# SmartRFv_25_06_15_PS.net
KiCad netlist of a schematic drawn in EAGLE
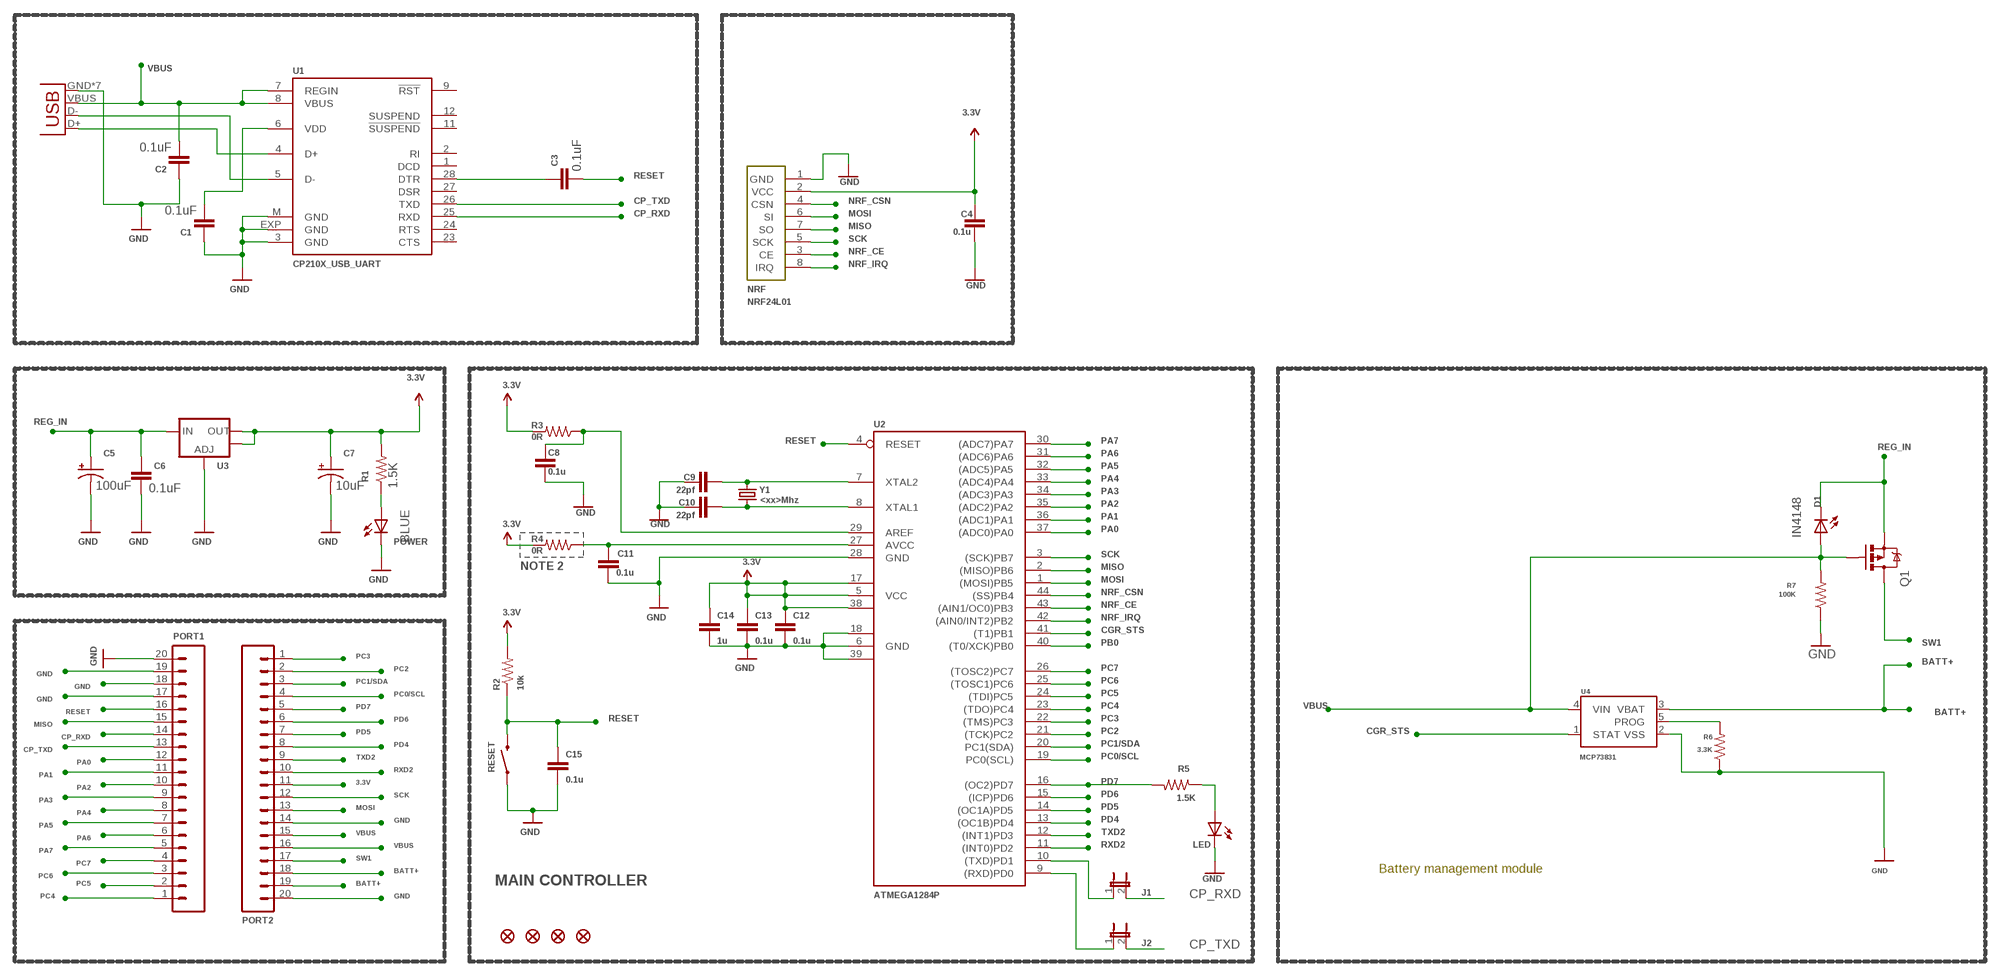
[diagram p0: schematic, sheet 1]

(export (version "E")
  (design (tool "Eeschema 10.0.6"))
  (components
    (comp (ref "C1")
      (value "0.1uF")
      (footprint "eagle-import:0805")
      (libsource (lib "eagle-import") (part "SparkFun-Passives_CAP0805"))
    )
    (comp (ref "C2")
      (value "0.1uF")
      (footprint "eagle-import:0805")
      (libsource (lib "eagle-import") (part "SparkFun-Passives_CAP0805"))
    )
    (comp (ref "C3")
      (value "0.1uF")
      (footprint "eagle-import:0805")
      (libsource (lib "eagle-import") (part "SparkFun-Passives_CAP0805"))
    )
    (comp (ref "C4")
      (value "0.1u")
      (footprint "eagle-import:0805")
      (libsource (lib "eagle-import") (part "CAP0805"))
    )
    (comp (ref "C5")
      (value "100uF")
      (footprint "eagle-import:EIA3216-KIT")
      (libsource (lib "eagle-import") (part "CAP_POL1206-KIT"))
    )
    (comp (ref "C6")
      (value "0.1uF")
      (footprint "eagle-import:0805")
      (libsource (lib "eagle-import") (part "SparkFun-Passives_CAP0805"))
    )
    (comp (ref "C7")
      (value "10uF")
      (footprint "eagle-import:EIA3216-KIT")
      (libsource (lib "eagle-import") (part "CAP_POL1206-KIT"))
    )
    (comp (ref "C8")
      (value "0.1u")
      (footprint "eagle-import:0805")
      (libsource (lib "eagle-import") (part "CAP0805"))
    )
    (comp (ref "C9")
      (value "22pf")
      (footprint "eagle-import:0805")
      (libsource (lib "eagle-import") (part "CAP0805"))
    )
    (comp (ref "C10")
      (value "22pf")
      (footprint "eagle-import:0805")
      (libsource (lib "eagle-import") (part "CAP0805"))
    )
    (comp (ref "C11")
      (value "0.1u")
      (footprint "eagle-import:0805")
      (libsource (lib "eagle-import") (part "CAP0805"))
    )
    (comp (ref "C12")
      (value "0.1u")
      (footprint "eagle-import:0805")
      (libsource (lib "eagle-import") (part "CAP0805"))
    )
    (comp (ref "C13")
      (value "0.1u")
      (footprint "eagle-import:0805")
      (libsource (lib "eagle-import") (part "CAP0805"))
    )
    (comp (ref "C14")
      (value "1u")
      (footprint "eagle-import:0805")
      (libsource (lib "eagle-import") (part "CAP0805"))
    )
    (comp (ref "C15")
      (value "0.1u")
      (footprint "eagle-import:0805")
      (libsource (lib "eagle-import") (part "CAP0805"))
    )
    (comp (ref "D1")
      (value "IN4148")
      (footprint "eagle-import:LED-1206")
      (libsource (lib "eagle-import") (part "LED1206"))
    )
    (comp (ref "FID1")
      (value "FIDUCIAL1X2")
      (footprint "eagle-import:FIDUCIAL-1X2")
      (libsource (lib "eagle-import") (part "FIDUCIAL1X2"))
    )
    (comp (ref "FID2")
      (value "FIDUCIAL1X2")
      (footprint "eagle-import:FIDUCIAL-1X2")
      (libsource (lib "eagle-import") (part "FIDUCIAL1X2"))
    )
    (comp (ref "FID3")
      (value "FIDUCIAL1X2")
      (footprint "eagle-import:FIDUCIAL-1X2")
      (libsource (lib "eagle-import") (part "FIDUCIAL1X2"))
    )
    (comp (ref "FID4")
      (value "FIDUCIAL1X2")
      (footprint "eagle-import:FIDUCIAL-1X2")
      (libsource (lib "eagle-import") (part "FIDUCIAL1X2"))
    )
    (comp (ref "J1")
      (value "JUMPER-2SMD-NC")
      (footprint "eagle-import:SJ_2S")
      (libsource (lib "eagle-import") (part "JUMPER-2SMD-NC"))
    )
    (comp (ref "J2")
      (value "JUMPER-2SMD-NC")
      (footprint "eagle-import:SJ_2S")
      (libsource (lib "eagle-import") (part "JUMPER-2SMD-NC"))
    )
    (comp (ref "LED")
      (value "LED")
      (footprint "eagle-import:LED-0805")
      (libsource (lib "eagle-import") (part "LED"))
    )
    (comp (ref "NRF")
      (value "NRF2401")
      (footprint "eagle-import:NRF2401")
      (fields (field (name "MFR_PN") "NRF24L01"))
      (libsource (lib "eagle-import") (part "NRF2401"))
    )
    (comp (ref "PORT1")
      (value "M20")
      (footprint "eagle-import:1X20")
      (libsource (lib "eagle-import") (part "M20"))
    )
    (comp (ref "PORT2")
      (value "M20")
      (footprint "eagle-import:1X20")
      (libsource (lib "eagle-import") (part "M20"))
    )
    (comp (ref "POWER")
      (value "BLUE")
      (footprint "eagle-import:LED-0805")
      (libsource (lib "eagle-import") (part "LED"))
    )
    (comp (ref "Q1")
      (value "MOSFET-PCHANNELSMD")
      (footprint "eagle-import:SOT23-3")
      (libsource (lib "eagle-import") (part "MOSFET-PCHANNELSMD"))
    )
    (comp (ref "R1")
      (value "1.5K")
      (footprint "eagle-import:0805")
      (libsource (lib "eagle-import") (part "RESISTOR0805-RES"))
    )
    (comp (ref "R2")
      (value "10k")
      (footprint "eagle-import:0805")
      (libsource (lib "eagle-import") (part "RESISTOR0805-RES"))
    )
    (comp (ref "R3")
      (value "0R")
      (footprint "eagle-import:0805")
      (libsource (lib "eagle-import") (part "RESISTOR0805-RES"))
    )
    (comp (ref "R4")
      (value "0R")
      (footprint "eagle-import:0805")
      (libsource (lib "eagle-import") (part "RESISTOR0805-RES"))
    )
    (comp (ref "R5")
      (value "1.5K")
      (footprint "eagle-import:0805")
      (libsource (lib "eagle-import") (part "RESISTOR0805-RES"))
    )
    (comp (ref "R6")
      (value "3.3K")
      (footprint "eagle-import:0805")
      (libsource (lib "eagle-import") (part "RESISTOR0805-RES"))
    )
    (comp (ref "R7")
      (value "100K")
      (footprint "eagle-import:0805")
      (libsource (lib "eagle-import") (part "RESISTOR0805-RES"))
    )
    (comp (ref "RESET")
      (value "SWITCH-MOMENTARY-2-SMD-1101NE")
      (footprint "eagle-import:TACTILE-SWITCH-1101NE")
      (libsource (lib "eagle-import") (part "SWITCH-MOMENTARY-2-SMD-1101NE"))
    )
    (comp (ref "U1")
      (value "CP210X_USB_UART")
      (footprint "eagle-import:MLP28")
      (libsource (lib "eagle-import") (part "CP210X_USB_UART"))
    )
    (comp (ref "U2")
      (value "MEGA32-A")
      (footprint "eagle-import:TQFP44")
      (fields (field (name "MPN") "ATMEGA32-16AU") (field (name "MPN_1") "ATMEGA1284P"))
      (libsource (lib "eagle-import") (part "MEGA32-A"))
    )
    (comp (ref "U3")
      (value "V_REG_LM1117SOT223")
      (footprint "eagle-import:SOT223")
      (libsource (lib "eagle-import") (part "V_REG_LM1117SOT223"))
    )
    (comp (ref "U4")
      (value "MCP73831")
      (footprint "eagle-import:SOT23-5")
      (libsource (lib "eagle-import") (part "MCP73831"))
    )
    (comp (ref "USB")
      (value "USB-MICROB")
      (footprint "eagle-import:USB-MICROB")
      (libsource (lib "eagle-import") (part "USB-MICROB"))
    )
    (comp (ref "Y1")
      (value "<xx>Mhz")
      (footprint "eagle-import:CRYSTAL-SMD-5X3")
      (libsource (lib "eagle-import") (part "CRYSTAL5X3"))
    )
  )
  (nets
    (net (code "1") (name "/BATT+") (class "Default")
      (node (ref "PORT2") (pin "18") (pinfunction "18_18") (pintype "passive"))
      (node (ref "PORT2") (pin "19") (pinfunction "19_19") (pintype "passive"))
      (node (ref "U4") (pin "3") (pinfunction "VBAT_3") (pintype "power_in"))
    )
    (net (code "2") (name "/CGR_STS") (class "Default")
      (node (ref "U2") (pin "41") (pinfunction "(T1)PB1_41") (pintype "bidirectional"))
      (node (ref "U4") (pin "1") (pinfunction "STAT_1") (pintype "output"))
    )
    (net (code "3") (name "/CP_RXD") (class "Default")
      (node (ref "J1") (pin "2") (pinfunction "2_2") (pintype "passive"))
      (node (ref "PORT1") (pin "14") (pinfunction "14_14") (pintype "passive"))
      (node (ref "U1") (pin "25") (pinfunction "RXD_25") (pintype "input"))
    )
    (net (code "4") (name "/CP_TXD") (class "Default")
      (node (ref "J2") (pin "2") (pinfunction "2_2") (pintype "passive"))
      (node (ref "PORT1") (pin "13") (pinfunction "13_13") (pintype "passive"))
      (node (ref "U1") (pin "26") (pinfunction "TXD_26") (pintype "output"))
    )
    (net (code "5") (name "/MISO") (class "Default")
      (node (ref "NRF") (pin "7") (pinfunction "SO_7") (pintype "bidirectional"))
      (node (ref "PORT1") (pin "15") (pinfunction "15_15") (pintype "passive"))
      (node (ref "U2") (pin "2") (pinfunction "(MISO)PB6_2") (pintype "bidirectional"))
    )
    (net (code "6") (name "/MOSI") (class "Default")
      (node (ref "NRF") (pin "6") (pinfunction "SI_6") (pintype "bidirectional"))
      (node (ref "PORT2") (pin "13") (pinfunction "13_13") (pintype "passive"))
      (node (ref "U2") (pin "1") (pinfunction "(MOSI)PB5_1") (pintype "bidirectional"))
    )
    (net (code "7") (name "/NRF_CE") (class "Default")
      (node (ref "NRF") (pin "3") (pinfunction "CE_3") (pintype "bidirectional"))
      (node (ref "U2") (pin "43") (pinfunction "(AIN1/OC0)PB3_43") (pintype "bidirectional"))
    )
    (net (code "8") (name "/NRF_CSN") (class "Default")
      (node (ref "NRF") (pin "4") (pinfunction "CSN_4") (pintype "bidirectional"))
      (node (ref "U2") (pin "44") (pinfunction "(SS)PB4_44") (pintype "bidirectional"))
    )
    (net (code "9") (name "/NRF_IRQ") (class "Default")
      (node (ref "NRF") (pin "8") (pinfunction "IRQ_8") (pintype "bidirectional"))
      (node (ref "U2") (pin "42") (pinfunction "(AIN0/INT2)PB2_42") (pintype "bidirectional"))
    )
    (net (code "10") (name "/PA0") (class "Default")
      (node (ref "PORT1") (pin "12") (pinfunction "12_12") (pintype "passive"))
      (node (ref "U2") (pin "37") (pinfunction "(ADC0)PA0_37") (pintype "bidirectional"))
    )
    (net (code "11") (name "/PA1") (class "Default")
      (node (ref "PORT1") (pin "11") (pinfunction "11_11") (pintype "passive"))
      (node (ref "U2") (pin "36") (pinfunction "(ADC1)PA1_36") (pintype "bidirectional"))
    )
    (net (code "12") (name "/PA2") (class "Default")
      (node (ref "PORT1") (pin "10") (pinfunction "10_10") (pintype "passive"))
      (node (ref "U2") (pin "35") (pinfunction "(ADC2)PA2_35") (pintype "bidirectional"))
    )
    (net (code "13") (name "/PA3") (class "Default")
      (node (ref "PORT1") (pin "9") (pinfunction "9_9") (pintype "passive"))
      (node (ref "U2") (pin "34") (pinfunction "(ADC3)PA3_34") (pintype "bidirectional"))
    )
    (net (code "14") (name "/PA4") (class "Default")
      (node (ref "PORT1") (pin "8") (pinfunction "8_8") (pintype "passive"))
      (node (ref "U2") (pin "33") (pinfunction "(ADC4)PA4_33") (pintype "bidirectional"))
    )
    (net (code "15") (name "/PA5") (class "Default")
      (node (ref "PORT1") (pin "7") (pinfunction "7_7") (pintype "passive"))
      (node (ref "U2") (pin "32") (pinfunction "(ADC5)PA5_32") (pintype "bidirectional"))
    )
    (net (code "16") (name "/PA6") (class "Default")
      (node (ref "PORT1") (pin "6") (pinfunction "6_6") (pintype "passive"))
      (node (ref "U2") (pin "31") (pinfunction "(ADC6)PA6_31") (pintype "bidirectional"))
    )
    (net (code "17") (name "/PA7") (class "Default")
      (node (ref "PORT1") (pin "5") (pinfunction "5_5") (pintype "passive"))
      (node (ref "U2") (pin "30") (pinfunction "(ADC7)PA7_30") (pintype "bidirectional"))
    )
    (net (code "18") (name "/PB0") (class "Default")
      (node (ref "U2") (pin "40") (pinfunction "(T0/XCK)PB0_40") (pintype "bidirectional"))
    )
    (net (code "19") (name "/PC0{slash}SCL") (class "Default")
      (node (ref "PORT2") (pin "4") (pinfunction "4_4") (pintype "passive"))
      (node (ref "U2") (pin "19") (pinfunction "PC0(SCL)_19") (pintype "bidirectional"))
    )
    (net (code "20") (name "/PC1{slash}SDA") (class "Default")
      (node (ref "PORT2") (pin "3") (pinfunction "3_3") (pintype "passive"))
      (node (ref "U2") (pin "20") (pinfunction "PC1(SDA)_20") (pintype "bidirectional"))
    )
    (net (code "21") (name "/PC2") (class "Default")
      (node (ref "PORT2") (pin "2") (pinfunction "2_2") (pintype "passive"))
      (node (ref "U2") (pin "21") (pinfunction "(TCK)PC2_21") (pintype "bidirectional"))
    )
    (net (code "22") (name "/PC3") (class "Default")
      (node (ref "PORT2") (pin "1") (pinfunction "1_1") (pintype "passive"))
      (node (ref "U2") (pin "22") (pinfunction "(TMS)PC3_22") (pintype "bidirectional"))
    )
    (net (code "23") (name "/PC4") (class "Default")
      (node (ref "PORT1") (pin "1") (pinfunction "1_1") (pintype "passive"))
      (node (ref "U2") (pin "23") (pinfunction "(TDO)PC4_23") (pintype "bidirectional"))
    )
    (net (code "24") (name "/PC5") (class "Default")
      (node (ref "PORT1") (pin "2") (pinfunction "2_2") (pintype "passive"))
      (node (ref "U2") (pin "24") (pinfunction "(TDI)PC5_24") (pintype "bidirectional"))
    )
    (net (code "25") (name "/PC6") (class "Default")
      (node (ref "PORT1") (pin "3") (pinfunction "3_3") (pintype "passive"))
      (node (ref "U2") (pin "25") (pinfunction "(TOSC1)PC6_25") (pintype "bidirectional"))
    )
    (net (code "26") (name "/PC7") (class "Default")
      (node (ref "PORT1") (pin "4") (pinfunction "4_4") (pintype "passive"))
      (node (ref "U2") (pin "26") (pinfunction "(TOSC2)PC7_26") (pintype "bidirectional"))
    )
    (net (code "27") (name "/PD4") (class "Default")
      (node (ref "PORT2") (pin "8") (pinfunction "8_8") (pintype "passive"))
      (node (ref "U2") (pin "13") (pinfunction "(OC1B)PD4_13") (pintype "bidirectional"))
    )
    (net (code "28") (name "/PD5") (class "Default")
      (node (ref "PORT2") (pin "7") (pinfunction "7_7") (pintype "passive"))
      (node (ref "U2") (pin "14") (pinfunction "(OC1A)PD5_14") (pintype "bidirectional"))
    )
    (net (code "29") (name "/PD6") (class "Default")
      (node (ref "PORT2") (pin "6") (pinfunction "6_6") (pintype "passive"))
      (node (ref "U2") (pin "15") (pinfunction "(ICP)PD6_15") (pintype "bidirectional"))
    )
    (net (code "30") (name "/PD7") (class "Default")
      (node (ref "PORT2") (pin "5") (pinfunction "5_5") (pintype "passive"))
      (node (ref "R5") (pin "2") (pinfunction "2_2") (pintype "passive"))
      (node (ref "U2") (pin "16") (pinfunction "(OC2)PD7_16") (pintype "bidirectional"))
    )
    (net (code "31") (name "/REG_IN") (class "Default")
      (node (ref "C5") (pin "A") (pinfunction "+_A") (pintype "passive"))
      (node (ref "C6") (pin "1") (pinfunction "1_1") (pintype "passive"))
      (node (ref "D1") (pin "C") (pinfunction "C_C") (pintype "passive"))
      (node (ref "Q1") (pin "2") (pinfunction "S_2") (pintype "passive"))
      (node (ref "U3") (pin "3") (pinfunction "IN_3") (pintype "input"))
    )
    (net (code "32") (name "/RESET") (class "Default")
      (node (ref "C15") (pin "1") (pinfunction "1_1") (pintype "passive"))
      (node (ref "C3") (pin "2") (pinfunction "2_2") (pintype "passive"))
      (node (ref "PORT1") (pin "16") (pinfunction "16_16") (pintype "passive"))
      (node (ref "R2") (pin "1") (pinfunction "1_1") (pintype "passive"))
      (node (ref "RESET") (pin "P$2") (pinfunction "2_P$2") (pintype "passive"))
      (node (ref "U2") (pin "4") (pinfunction "RESET_4") (pintype "input"))
    )
    (net (code "33") (name "/RXD2") (class "Default")
      (node (ref "PORT2") (pin "10") (pinfunction "10_10") (pintype "passive"))
      (node (ref "U2") (pin "11") (pinfunction "(INT0)PD2_11") (pintype "bidirectional"))
    )
    (net (code "34") (name "/SCK") (class "Default")
      (node (ref "NRF") (pin "5") (pinfunction "SCK_5") (pintype "bidirectional"))
      (node (ref "PORT2") (pin "12") (pinfunction "12_12") (pintype "passive"))
      (node (ref "U2") (pin "3") (pinfunction "(SCK)PB7_3") (pintype "bidirectional"))
    )
    (net (code "35") (name "/SW1") (class "Default")
      (node (ref "PORT2") (pin "17") (pinfunction "17_17") (pintype "passive"))
      (node (ref "Q1") (pin "3") (pinfunction "D_3") (pintype "passive"))
    )
    (net (code "36") (name "/TXD2") (class "Default")
      (node (ref "PORT2") (pin "9") (pinfunction "9_9") (pintype "passive"))
      (node (ref "U2") (pin "12") (pinfunction "(INT1)PD3_12") (pintype "bidirectional"))
    )
    (net (code "37") (name "/VBUS") (class "Default")
      (node (ref "C2") (pin "2") (pinfunction "2_2") (pintype "passive"))
      (node (ref "D1") (pin "A") (pinfunction "A_A") (pintype "passive"))
      (node (ref "PORT2") (pin "15") (pinfunction "15_15") (pintype "passive"))
      (node (ref "PORT2") (pin "16") (pinfunction "16_16") (pintype "passive"))
      (node (ref "Q1") (pin "1") (pinfunction "G_1") (pintype "passive"))
      (node (ref "R7") (pin "2") (pinfunction "2_2") (pintype "passive"))
      (node (ref "U1") (pin "7") (pinfunction "REGIN_7") (pintype "passive"))
      (node (ref "U1") (pin "8") (pinfunction "VBUS_8") (pintype "input"))
      (node (ref "U4") (pin "4") (pinfunction "VIN_4") (pintype "power_in"))
      (node (ref "USB") (pin "VBUS") (pinfunction "VBUS_VBUS") (pintype "bidirectional"))
    )
    (net (code "38") (name "3.3V") (class "Default")
      (node (ref "C12") (pin "1") (pinfunction "1_1") (pintype "passive"))
      (node (ref "C13") (pin "1") (pinfunction "1_1") (pintype "passive"))
      (node (ref "C14") (pin "1") (pinfunction "1_1") (pintype "passive"))
      (node (ref "C4") (pin "2") (pinfunction "2_2") (pintype "passive"))
      (node (ref "C7") (pin "A") (pinfunction "+_A") (pintype "passive"))
      (node (ref "NRF") (pin "2") (pinfunction "VCC_2") (pintype "bidirectional"))
      (node (ref "PORT2") (pin "11") (pinfunction "11_11") (pintype "passive"))
      (node (ref "R1") (pin "2") (pinfunction "2_2") (pintype "passive"))
      (node (ref "R2") (pin "2") (pinfunction "2_2") (pintype "passive"))
      (node (ref "R3") (pin "2") (pinfunction "2_2") (pintype "passive"))
      (node (ref "R4") (pin "2") (pinfunction "2_2") (pintype "passive"))
      (node (ref "U2") (pin "17") (pinfunction "VCC1_17") (pintype "power_in"))
      (node (ref "U2") (pin "38") (pinfunction "VCC2_38") (pintype "power_in"))
      (node (ref "U2") (pin "5") (pinfunction "VCC_5") (pintype "power_in"))
      (node (ref "U3") (pin "2") (pinfunction "OUT_2") (pintype "output"))
      (node (ref "U3") (pin "4") (pinfunction "OUT_4") (pintype "output"))
    )
    (net (code "39") (name "GND") (class "Default")
      (node (ref "C1") (pin "1") (pinfunction "1_1") (pintype "passive"))
      (node (ref "C10") (pin "1") (pinfunction "1_1") (pintype "passive"))
      (node (ref "C11") (pin "2") (pinfunction "2_2") (pintype "passive"))
      (node (ref "C12") (pin "2") (pinfunction "2_2") (pintype "passive"))
      (node (ref "C13") (pin "2") (pinfunction "2_2") (pintype "passive"))
      (node (ref "C14") (pin "2") (pinfunction "2_2") (pintype "passive"))
      (node (ref "C15") (pin "2") (pinfunction "2_2") (pintype "passive"))
      (node (ref "C2") (pin "1") (pinfunction "1_1") (pintype "passive"))
      (node (ref "C4") (pin "1") (pinfunction "1_1") (pintype "passive"))
      (node (ref "C5") (pin "C") (pinfunction "-_C") (pintype "passive"))
      (node (ref "C6") (pin "2") (pinfunction "2_2") (pintype "passive"))
      (node (ref "C7") (pin "C") (pinfunction "-_C") (pintype "passive"))
      (node (ref "C8") (pin "2") (pinfunction "2_2") (pintype "passive"))
      (node (ref "C9") (pin "1") (pinfunction "1_1") (pintype "passive"))
      (node (ref "LED") (pin "2") (pinfunction "C_2") (pintype "passive"))
      (node (ref "NRF") (pin "1") (pinfunction "GND_1") (pintype "bidirectional"))
      (node (ref "PORT1") (pin "17") (pinfunction "17_17") (pintype "passive"))
      (node (ref "PORT1") (pin "18") (pinfunction "18_18") (pintype "passive"))
      (node (ref "PORT1") (pin "19") (pinfunction "19_19") (pintype "passive"))
      (node (ref "PORT1") (pin "20") (pinfunction "20_20") (pintype "passive"))
      (node (ref "PORT2") (pin "14") (pinfunction "14_14") (pintype "passive"))
      (node (ref "PORT2") (pin "20") (pinfunction "20_20") (pintype "passive"))
      (node (ref "POWER") (pin "2") (pinfunction "C_2") (pintype "passive"))
      (node (ref "R6") (pin "1") (pinfunction "1_1") (pintype "passive"))
      (node (ref "R7") (pin "1") (pinfunction "1_1") (pintype "passive"))
      (node (ref "RESET") (pin "P$1") (pinfunction "1_P$1") (pintype "passive"))
      (node (ref "U1") (pin "3") (pinfunction "GND_3") (pintype "power_in"))
      (node (ref "U1") (pin "EXP") (pinfunction "GND_EXP") (pintype "power_in"))
      (node (ref "U1") (pin "M") (pinfunction "GND_M") (pintype "power_in"))
      (node (ref "U2") (pin "18") (pinfunction "GND1_18") (pintype "power_in"))
      (node (ref "U2") (pin "28") (pinfunction "GND_28") (pintype "power_in"))
      (node (ref "U2") (pin "39") (pinfunction "GND2_39") (pintype "power_in"))
      (node (ref "U2") (pin "6") (pinfunction "GND_6") (pintype "power_in"))
      (node (ref "U3") (pin "1") (pinfunction "ADJ_1") (pintype "input"))
      (node (ref "U4") (pin "2") (pinfunction "VSS_2") (pintype "power_in"))
      (node (ref "USB") (pin "GND") (pinfunction "GND_GND") (pintype "bidirectional"))
      (node (ref "USB") (pin "MT1") (pinfunction "GND_MT1") (pintype "bidirectional"))
      (node (ref "USB") (pin "MT2") (pinfunction "GND_MT2") (pintype "bidirectional"))
      (node (ref "USB") (pin "MT3") (pinfunction "GND_MT3") (pintype "bidirectional"))
      (node (ref "USB") (pin "MT4") (pinfunction "GND_MT4") (pintype "bidirectional"))
      (node (ref "USB") (pin "P$1") (pinfunction "GND_P$1") (pintype "bidirectional"))
      (node (ref "USB") (pin "P$2") (pinfunction "GND_P$2") (pintype "bidirectional"))
    )
    (net (code "40") (name "Net-(LED-A)") (class "Default")
      (node (ref "LED") (pin "1") (pinfunction "A_1") (pintype "passive"))
      (node (ref "R5") (pin "1") (pinfunction "1_1") (pintype "passive"))
    )
    (net (code "41") (name "Net-(POWER-A)") (class "Default")
      (node (ref "POWER") (pin "1") (pinfunction "A_1") (pintype "passive"))
      (node (ref "R1") (pin "1") (pinfunction "1_1") (pintype "passive"))
    )
    (net (code "42") (name "Net-(U1-D+)") (class "Default")
      (node (ref "U1") (pin "4") (pinfunction "D+_4") (pintype "bidirectional"))
      (node (ref "USB") (pin "D+") (pinfunction "D+_D+") (pintype "bidirectional"))
    )
    (net (code "43") (name "Net-(U1-D-)") (class "Default")
      (node (ref "U1") (pin "5") (pinfunction "D-_5") (pintype "bidirectional"))
      (node (ref "USB") (pin "D-") (pinfunction "D-_D-") (pintype "bidirectional"))
    )
    (net (code "44") (name "Net-(U1-DTR)") (class "Default")
      (node (ref "C3") (pin "1") (pinfunction "1_1") (pintype "passive"))
      (node (ref "U1") (pin "28") (pinfunction "DTR_28") (pintype "output"))
    )
    (net (code "45") (name "Net-(U1-VDD)") (class "Default")
      (node (ref "C1") (pin "2") (pinfunction "2_2") (pintype "passive"))
      (node (ref "U1") (pin "6") (pinfunction "VDD_6") (pintype "power_in"))
    )
    (net (code "46") (name "Net-(U2-(RXD)PD0)") (class "Default")
      (node (ref "J2") (pin "1") (pinfunction "1_1") (pintype "passive"))
      (node (ref "U2") (pin "9") (pinfunction "(RXD)PD0_9") (pintype "bidirectional"))
    )
    (net (code "47") (name "Net-(U2-(TXD)PD1)") (class "Default")
      (node (ref "J1") (pin "1") (pinfunction "1_1") (pintype "passive"))
      (node (ref "U2") (pin "10") (pinfunction "(TXD)PD1_10") (pintype "bidirectional"))
    )
    (net (code "48") (name "Net-(U2-AREF)") (class "Default")
      (node (ref "C8") (pin "1") (pinfunction "1_1") (pintype "passive"))
      (node (ref "R3") (pin "1") (pinfunction "1_1") (pintype "passive"))
      (node (ref "U2") (pin "29") (pinfunction "AREF_29") (pintype "passive"))
    )
    (net (code "49") (name "Net-(U2-AVCC)") (class "Default")
      (node (ref "C11") (pin "1") (pinfunction "1_1") (pintype "passive"))
      (node (ref "R4") (pin "1") (pinfunction "1_1") (pintype "passive"))
      (node (ref "U2") (pin "27") (pinfunction "AVCC_27") (pintype "power_in"))
    )
    (net (code "50") (name "Net-(U2-XTAL1)") (class "Default")
      (node (ref "C10") (pin "2") (pinfunction "2_2") (pintype "passive"))
      (node (ref "U2") (pin "8") (pinfunction "XTAL1_8") (pintype "bidirectional"))
      (node (ref "Y1") (pin "1") (pinfunction "1_1") (pintype "passive"))
    )
    (net (code "51") (name "Net-(U2-XTAL2)") (class "Default")
      (node (ref "C9") (pin "2") (pinfunction "2_2") (pintype "passive"))
      (node (ref "U2") (pin "7") (pinfunction "XTAL2_7") (pintype "bidirectional"))
      (node (ref "Y1") (pin "3") (pinfunction "2_3") (pintype "passive"))
    )
    (net (code "52") (name "Net-(U4-PROG)") (class "Default")
      (node (ref "R6") (pin "2") (pinfunction "2_2") (pintype "passive"))
      (node (ref "U4") (pin "5") (pinfunction "PROG_5") (pintype "input"))
    )
    (net (code "53") (name "unconnected-(U1-CTS-Pad23)") (class "Default")
      (node (ref "U1") (pin "23") (pinfunction "CTS_23") (pintype "input"))
    )
    (net (code "54") (name "unconnected-(U1-DCD-Pad1)") (class "Default")
      (node (ref "U1") (pin "1") (pinfunction "DCD_1") (pintype "input"))
    )
    (net (code "55") (name "unconnected-(U1-DSR-Pad27)") (class "Default")
      (node (ref "U1") (pin "27") (pinfunction "DSR_27") (pintype "input"))
    )
    (net (code "56") (name "unconnected-(U1-RI-Pad2)") (class "Default")
      (node (ref "U1") (pin "2") (pinfunction "RI_2") (pintype "input"))
    )
    (net (code "57") (name "unconnected-(U1-RTS-Pad24)") (class "Default")
      (node (ref "U1") (pin "24") (pinfunction "RTS_24") (pintype "output"))
    )
    (net (code "58") (name "unconnected-(U1-SUSPEND-Pad12)") (class "Default")
      (node (ref "U1") (pin "12") (pinfunction "SUSPEND_12") (pintype "output"))
    )
    (net (code "59") (name "unconnected-(U1-~{RST}-Pad9)") (class "Default")
      (node (ref "U1") (pin "9") (pinfunction "~{RST}_9") (pintype "bidirectional"))
    )
    (net (code "60") (name "unconnected-(U1-~{SUSPEND}-Pad11)") (class "Default")
      (node (ref "U1") (pin "11") (pinfunction "~{SUSPEND}_11") (pintype "output"))
    )
  )
)
